# fulldrive2.net
KiCad netlist of a schematic drawn in EAGLE
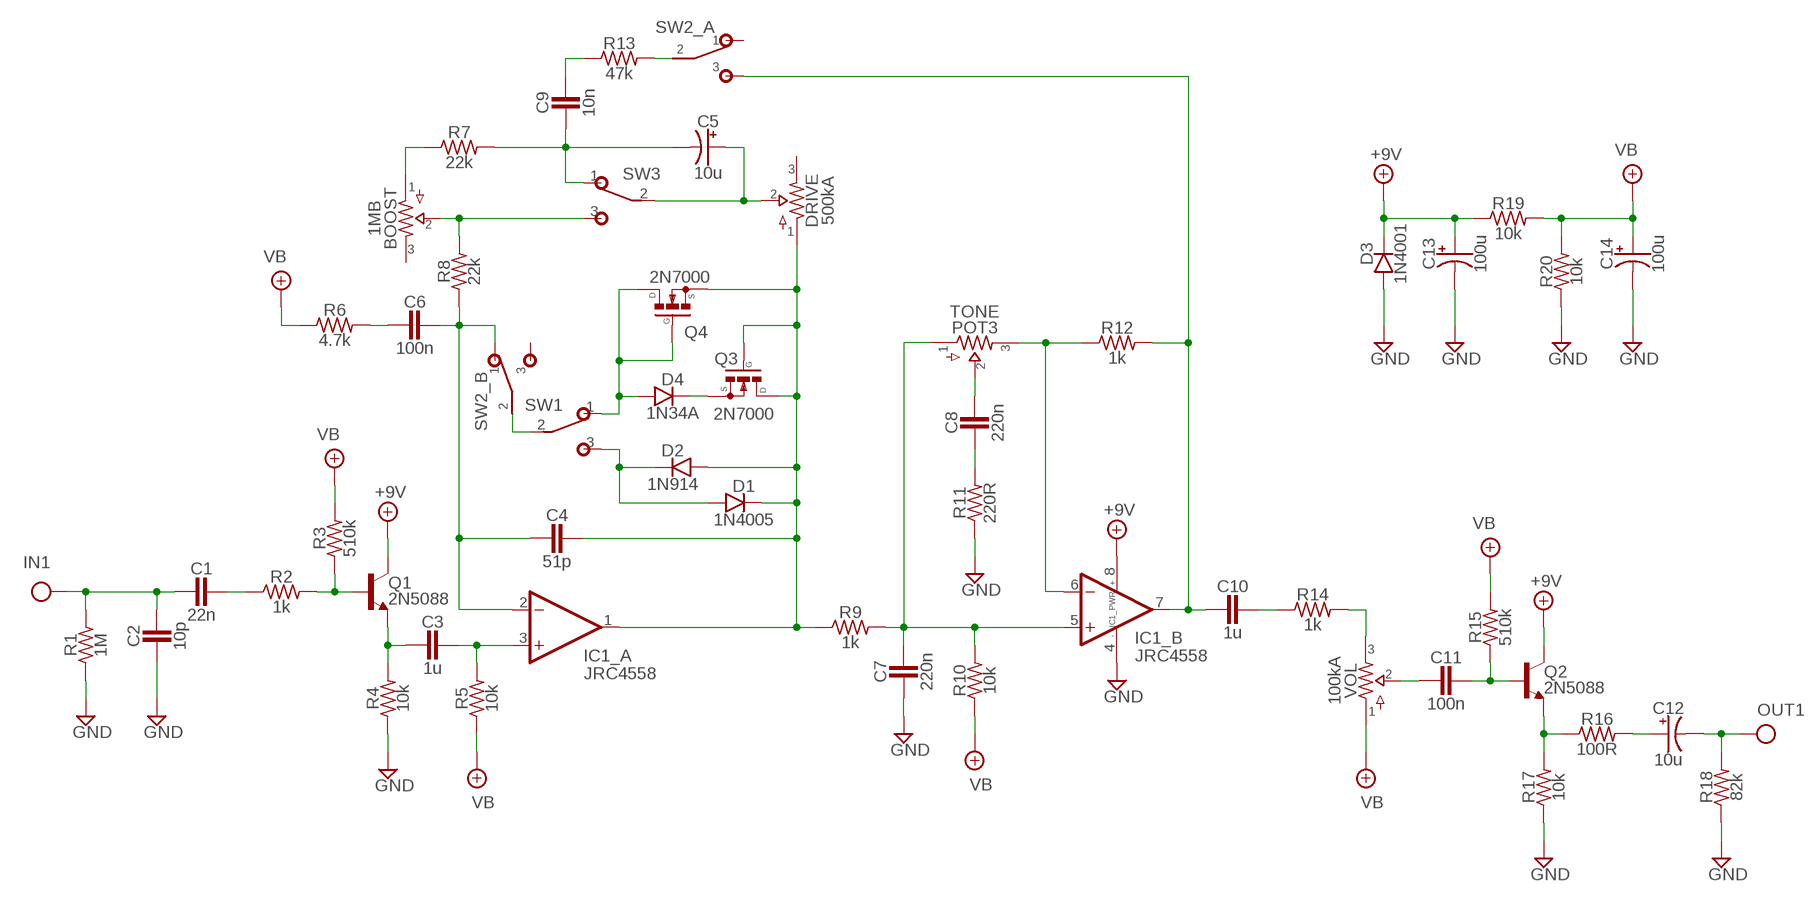
[diagram p0: schematic, sheet 1]

(export (version "E")
  (design (tool "Eeschema 10.0.6"))
  (components
    (comp (ref "BOOST")
      (value "1MB")
      (footprint "eagle-import:16MM")
      (libsource (lib "eagle-import") (part "POTS16MM"))
    )
    (comp (ref "C1")
      (value "22n")
      (footprint "eagle-import:BOX_SMALL")
      (libsource (lib "eagle-import") (part "CER/FILMBOX.1"))
    )
    (comp (ref "C2")
      (value "10p")
      (footprint "eagle-import:BOX_SMALL")
      (libsource (lib "eagle-import") (part "CER/FILMBOX.1"))
    )
    (comp (ref "C3")
      (value "1u")
      (footprint "eagle-import:BOX_SMALL")
      (libsource (lib "eagle-import") (part "CER/FILMBOX.1"))
    )
    (comp (ref "C4")
      (value "51p")
      (footprint "eagle-import:BOX_SMALL")
      (libsource (lib "eagle-import") (part "CER/FILMBOX.1"))
    )
    (comp (ref "C5")
      (value "10u")
      (footprint "eagle-import:050_020")
      (libsource (lib "eagle-import") (part "0500"))
    )
    (comp (ref "C6")
      (value "100n")
      (footprint "eagle-import:BOX_SMALL")
      (libsource (lib "eagle-import") (part "CER/FILMBOX.1"))
    )
    (comp (ref "C7")
      (value "220n")
      (footprint "eagle-import:BOX_SMALL")
      (libsource (lib "eagle-import") (part "CER/FILMBOX.1"))
    )
    (comp (ref "C8")
      (value "220n")
      (footprint "eagle-import:BOX_SMALL")
      (libsource (lib "eagle-import") (part "CER/FILMBOX.1"))
    )
    (comp (ref "C9")
      (value "10n")
      (footprint "eagle-import:BOX_SMALL")
      (libsource (lib "eagle-import") (part "CER/FILMBOX.1"))
    )
    (comp (ref "C10")
      (value "1u")
      (footprint "eagle-import:BOX_SMALL")
      (libsource (lib "eagle-import") (part "CER/FILMBOX.1"))
    )
    (comp (ref "C11")
      (value "100n")
      (footprint "eagle-import:BOX_SMALL")
      (libsource (lib "eagle-import") (part "CER/FILMBOX.1"))
    )
    (comp (ref "C12")
      (value "10u")
      (footprint "eagle-import:050_020")
      (libsource (lib "eagle-import") (part "0500"))
    )
    (comp (ref "C13")
      (value "100u")
      (footprint "eagle-import:050_020")
      (libsource (lib "eagle-import") (part "0500"))
    )
    (comp (ref "C14")
      (value "100u")
      (footprint "eagle-import:050_020")
      (libsource (lib "eagle-import") (part "0500"))
    )
    (comp (ref "D1")
      (value "1N4005")
      (footprint "eagle-import:DO35-2")
      (libsource (lib "eagle-import") (part "DO35.2"))
    )
    (comp (ref "D2")
      (value "1N914")
      (footprint "eagle-import:DO35-2")
      (libsource (lib "eagle-import") (part "DO35.2"))
    )
    (comp (ref "D3")
      (value "1N4001")
      (footprint "eagle-import:DO35-3")
      (libsource (lib "eagle-import") (part "DO35.3"))
    )
    (comp (ref "D4")
      (value "1N34A")
      (footprint "eagle-import:DO35-2")
      (libsource (lib "eagle-import") (part "DO35.2"))
    )
    (comp (ref "DRIVE")
      (value "500kA")
      (footprint "eagle-import:16MM")
      (libsource (lib "eagle-import") (part "POTS16MM"))
    )
    (comp (ref "IC1")
      (value "JRC4558")
      (footprint "eagle-import:DIL0")
      (libsource (lib "eagle-import") (part "DUALTH"))
    )
    (comp (ref "POT3")
      (value "TONE")
      (footprint "eagle-import:16MM")
      (libsource (lib "eagle-import") (part "POTS16MM"))
    )
    (comp (ref "Q1")
      (value "2N5088")
      (footprint "eagle-import:TO92-")
      (libsource (lib "eagle-import") (part "2N5088"))
    )
    (comp (ref "Q2")
      (value "2N5088")
      (footprint "eagle-import:TO92-")
      (libsource (lib "eagle-import") (part "2N5088"))
    )
    (comp (ref "Q3")
      (value "2N7000")
      (footprint "eagle-import:TO92-")
      (libsource (lib "eagle-import") (part "2N7000"))
    )
    (comp (ref "Q4")
      (value "2N7000")
      (footprint "eagle-import:TO92-")
      (libsource (lib "eagle-import") (part "2N7000"))
    )
    (comp (ref "R1")
      (value "1M")
      (footprint "eagle-import:R0207_3")
      (libsource (lib "eagle-import") (part "R_.3B"))
    )
    (comp (ref "R2")
      (value "1k")
      (footprint "eagle-import:R0207_3")
      (libsource (lib "eagle-import") (part "R_.3B"))
    )
    (comp (ref "R3")
      (value "510k")
      (footprint "eagle-import:R0207_3")
      (libsource (lib "eagle-import") (part "R_.3B"))
    )
    (comp (ref "R4")
      (value "10k")
      (footprint "eagle-import:R0207_3")
      (libsource (lib "eagle-import") (part "R_.3B"))
    )
    (comp (ref "R5")
      (value "10k")
      (footprint "eagle-import:R0207_3")
      (libsource (lib "eagle-import") (part "R_.3B"))
    )
    (comp (ref "R6")
      (value "4.7k")
      (footprint "eagle-import:R0207_3")
      (libsource (lib "eagle-import") (part "R_.3B"))
    )
    (comp (ref "R7")
      (value "22k")
      (footprint "eagle-import:R0207_3")
      (libsource (lib "eagle-import") (part "R_.3B"))
    )
    (comp (ref "R8")
      (value "22k")
      (footprint "eagle-import:R0207_3")
      (libsource (lib "eagle-import") (part "R_.3B"))
    )
    (comp (ref "R9")
      (value "1k")
      (footprint "eagle-import:R0207_3")
      (libsource (lib "eagle-import") (part "R_.3B"))
    )
    (comp (ref "R10")
      (value "10k")
      (footprint "eagle-import:R0207_3")
      (libsource (lib "eagle-import") (part "R_.3B"))
    )
    (comp (ref "R11")
      (value "220R")
      (footprint "eagle-import:R0207_3")
      (libsource (lib "eagle-import") (part "R_.3B"))
    )
    (comp (ref "R12")
      (value "1k")
      (footprint "eagle-import:R0207_3")
      (libsource (lib "eagle-import") (part "R_.3B"))
    )
    (comp (ref "R13")
      (value "47k")
      (footprint "eagle-import:R0207_3")
      (libsource (lib "eagle-import") (part "R_.3B"))
    )
    (comp (ref "R14")
      (value "1k")
      (footprint "eagle-import:R0207_3")
      (libsource (lib "eagle-import") (part "R_.3B"))
    )
    (comp (ref "R15")
      (value "510k")
      (footprint "eagle-import:R0207_3")
      (libsource (lib "eagle-import") (part "R_.3B"))
    )
    (comp (ref "R16")
      (value "100R")
      (footprint "eagle-import:R0207_3")
      (libsource (lib "eagle-import") (part "R_.3B"))
    )
    (comp (ref "R17")
      (value "10k")
      (footprint "eagle-import:R0207_3")
      (libsource (lib "eagle-import") (part "R_.3B"))
    )
    (comp (ref "R18")
      (value "82k")
      (footprint "eagle-import:R0207_3")
      (libsource (lib "eagle-import") (part "R_.3B"))
    )
    (comp (ref "R19")
      (value "10k")
      (footprint "eagle-import:R0207_3")
      (libsource (lib "eagle-import") (part "R_.3B"))
    )
    (comp (ref "R20")
      (value "10k")
      (footprint "eagle-import:R0207_3")
      (libsource (lib "eagle-import") (part "R_.3B"))
    )
    (comp (ref "SW1")
      (value "SPDT")
      (footprint "eagle-import:M9040P")
      (libsource (lib "eagle-import") (part "SPDT"))
    )
    (comp (ref "SW2")
      (value "DPDT")
      (footprint "eagle-import:DPDT")
      (libsource (lib "eagle-import") (part "DPDT"))
    )
    (comp (ref "SW3")
      (value "SPDT")
      (footprint "eagle-import:M9040P")
      (libsource (lib "eagle-import") (part "SPDT"))
    )
    (comp (ref "VOL")
      (value "100kA")
      (footprint "eagle-import:16MM")
      (libsource (lib "eagle-import") (part "POTS16MM"))
    )
  )
  (nets
    (net (code "1") (name "+9V") (class "Default")
      (node (ref "C13") (pin "+") (pinfunction "+_+") (pintype "passive"))
      (node (ref "D3") (pin "C") (pinfunction "C_C") (pintype "passive"))
      (node (ref "IC1") (pin "8") (pinfunction "V+_8") (pintype "power_in"))
      (node (ref "Q1") (pin "1") (pinfunction "C_1") (pintype "passive"))
      (node (ref "Q2") (pin "1") (pinfunction "C_1") (pintype "passive"))
      (node (ref "R19") (pin "1") (pinfunction "1_1") (pintype "passive"))
    )
    (net (code "2") (name "GND") (class "Default")
      (node (ref "C13") (pin "-") (pinfunction "-_-") (pintype "passive"))
      (node (ref "C14") (pin "-") (pinfunction "-_-") (pintype "passive"))
      (node (ref "C2") (pin "2") (pinfunction "2_2") (pintype "passive"))
      (node (ref "C7") (pin "2") (pinfunction "2_2") (pintype "passive"))
      (node (ref "D3") (pin "A") (pinfunction "A_A") (pintype "passive"))
      (node (ref "IC1") (pin "4") (pinfunction "V-_4") (pintype "power_in"))
      (node (ref "R1") (pin "1") (pinfunction "1_1") (pintype "passive"))
      (node (ref "R11") (pin "1") (pinfunction "1_1") (pintype "passive"))
      (node (ref "R17") (pin "1") (pinfunction "1_1") (pintype "passive"))
      (node (ref "R18") (pin "1") (pinfunction "1_1") (pintype "passive"))
      (node (ref "R20") (pin "1") (pinfunction "1_1") (pintype "passive"))
      (node (ref "R4") (pin "1") (pinfunction "1_1") (pintype "passive"))
    )
    (net (code "3") (name "IN") (class "Default")
      (node (ref "C1") (pin "2") (pinfunction "2_2") (pintype "passive"))
      (node (ref "C2") (pin "1") (pinfunction "1_1") (pintype "passive"))
      (node (ref "R1") (pin "2") (pinfunction "2_2") (pintype "passive"))
    )
    (net (code "4") (name "Net-(BOOST-Pad1)") (class "Default")
      (node (ref "BOOST") (pin "1") (pinfunction "1_1") (pintype "passive"))
      (node (ref "R7") (pin "1") (pinfunction "1_1") (pintype "passive"))
    )
    (net (code "5") (name "Net-(C1-Pad1)") (class "Default")
      (node (ref "C1") (pin "1") (pinfunction "1_1") (pintype "passive"))
      (node (ref "R2") (pin "1") (pinfunction "1_1") (pintype "passive"))
    )
    (net (code "6") (name "Net-(C6-Pad2)") (class "Default")
      (node (ref "C6") (pin "2") (pinfunction "2_2") (pintype "passive"))
      (node (ref "R6") (pin "2") (pinfunction "2_2") (pintype "passive"))
    )
    (net (code "7") (name "Net-(C8-Pad1)") (class "Default")
      (node (ref "C8") (pin "1") (pinfunction "1_1") (pintype "passive"))
      (node (ref "POT3") (pin "2") (pinfunction "2_2") (pintype "passive"))
    )
    (net (code "8") (name "Net-(C8-Pad2)") (class "Default")
      (node (ref "C8") (pin "2") (pinfunction "2_2") (pintype "passive"))
      (node (ref "R11") (pin "2") (pinfunction "2_2") (pintype "passive"))
    )
    (net (code "9") (name "Net-(C9-Pad1)") (class "Default")
      (node (ref "C9") (pin "1") (pinfunction "1_1") (pintype "passive"))
      (node (ref "R13") (pin "1") (pinfunction "1_1") (pintype "passive"))
    )
    (net (code "10") (name "Net-(C10-Pad1)") (class "Default")
      (node (ref "C10") (pin "1") (pinfunction "1_1") (pintype "passive"))
      (node (ref "R14") (pin "1") (pinfunction "1_1") (pintype "passive"))
    )
    (net (code "11") (name "Net-(C11-Pad2)") (class "Default")
      (node (ref "C11") (pin "2") (pinfunction "2_2") (pintype "passive"))
      (node (ref "VOL") (pin "2") (pinfunction "2_2") (pintype "passive"))
    )
    (net (code "12") (name "Net-(C12-Pad+)") (class "Default")
      (node (ref "C12") (pin "+") (pinfunction "+_+") (pintype "passive"))
      (node (ref "R16") (pin "2") (pinfunction "2_2") (pintype "passive"))
    )
    (net (code "13") (name "Net-(IC1A-+IN)") (class "Default")
      (node (ref "C3") (pin "1") (pinfunction "1_1") (pintype "passive"))
      (node (ref "IC1") (pin "3") (pinfunction "+IN_3") (pintype "input"))
      (node (ref "R5") (pin "2") (pinfunction "2_2") (pintype "passive"))
    )
    (net (code "14") (name "Net-(IC1A--IN)") (class "Default")
      (node (ref "C4") (pin "2") (pinfunction "2_2") (pintype "passive"))
      (node (ref "C6") (pin "1") (pinfunction "1_1") (pintype "passive"))
      (node (ref "IC1") (pin "2") (pinfunction "-IN_2") (pintype "input"))
      (node (ref "R8") (pin "1") (pinfunction "1_1") (pintype "passive"))
      (node (ref "SW2") (pin "B1") (pinfunction "1_B1") (pintype "passive"))
    )
    (net (code "15") (name "Net-(IC1A-OUT)") (class "Default")
      (node (ref "C4") (pin "1") (pinfunction "1_1") (pintype "passive"))
      (node (ref "D1") (pin "C") (pinfunction "C_C") (pintype "passive"))
      (node (ref "D2") (pin "A") (pinfunction "A_A") (pintype "passive"))
      (node (ref "DRIVE") (pin "1") (pinfunction "1_1") (pintype "passive"))
      (node (ref "IC1") (pin "1") (pinfunction "OUT_1") (pintype "output"))
      (node (ref "Q3") (pin "1") (pinfunction "D_1") (pintype "passive"))
      (node (ref "Q3") (pin "2") (pinfunction "G_2") (pintype "passive"))
      (node (ref "Q4") (pin "3") (pinfunction "S_3") (pintype "passive"))
      (node (ref "R9") (pin "1") (pinfunction "1_1") (pintype "passive"))
    )
    (net (code "16") (name "Net-(IC1B-+IN)") (class "Default")
      (node (ref "C7") (pin "1") (pinfunction "1_1") (pintype "passive"))
      (node (ref "IC1") (pin "5") (pinfunction "+IN_5") (pintype "input"))
      (node (ref "POT3") (pin "1") (pinfunction "1_1") (pintype "passive"))
      (node (ref "R10") (pin "2") (pinfunction "2_2") (pintype "passive"))
      (node (ref "R9") (pin "2") (pinfunction "2_2") (pintype "passive"))
    )
    (net (code "17") (name "Net-(IC1B--IN)") (class "Default")
      (node (ref "IC1") (pin "6") (pinfunction "-IN_6") (pintype "input"))
      (node (ref "POT3") (pin "3") (pinfunction "3_3") (pintype "passive"))
      (node (ref "R12") (pin "1") (pinfunction "1_1") (pintype "passive"))
    )
    (net (code "18") (name "Net-(IC1B-OUT)") (class "Default")
      (node (ref "C10") (pin "2") (pinfunction "2_2") (pintype "passive"))
      (node (ref "IC1") (pin "7") (pinfunction "OUT_7") (pintype "output"))
      (node (ref "R12") (pin "2") (pinfunction "2_2") (pintype "passive"))
      (node (ref "SW2") (pin "A3") (pinfunction "3_A3") (pintype "passive"))
    )
    (net (code "19") (name "Net-(Q1-B)") (class "Default")
      (node (ref "Q1") (pin "2") (pinfunction "B_2") (pintype "passive"))
      (node (ref "R2") (pin "2") (pinfunction "2_2") (pintype "passive"))
      (node (ref "R3") (pin "1") (pinfunction "1_1") (pintype "passive"))
    )
    (net (code "20") (name "Net-(Q1-E)") (class "Default")
      (node (ref "C3") (pin "2") (pinfunction "2_2") (pintype "passive"))
      (node (ref "Q1") (pin "3") (pinfunction "E_3") (pintype "passive"))
      (node (ref "R4") (pin "2") (pinfunction "2_2") (pintype "passive"))
    )
    (net (code "21") (name "Net-(Q2-B)") (class "Default")
      (node (ref "C11") (pin "1") (pinfunction "1_1") (pintype "passive"))
      (node (ref "Q2") (pin "2") (pinfunction "B_2") (pintype "passive"))
      (node (ref "R15") (pin "1") (pinfunction "1_1") (pintype "passive"))
    )
    (net (code "22") (name "Net-(Q2-E)") (class "Default")
      (node (ref "Q2") (pin "3") (pinfunction "E_3") (pintype "passive"))
      (node (ref "R16") (pin "1") (pinfunction "1_1") (pintype "passive"))
      (node (ref "R17") (pin "2") (pinfunction "2_2") (pintype "passive"))
    )
    (net (code "23") (name "Net-(Q3-S)") (class "Default")
      (node (ref "D4") (pin "C") (pinfunction "C_C") (pintype "passive"))
      (node (ref "Q3") (pin "3") (pinfunction "S_3") (pintype "passive"))
    )
    (net (code "24") (name "Net-(Q4-D)") (class "Default")
      (node (ref "D4") (pin "A") (pinfunction "A_A") (pintype "passive"))
      (node (ref "Q4") (pin "1") (pinfunction "D_1") (pintype "passive"))
      (node (ref "Q4") (pin "2") (pinfunction "G_2") (pintype "passive"))
      (node (ref "SW1") (pin "1") (pinfunction "O_1") (pintype "passive"))
    )
    (net (code "25") (name "Net-(R14-Pad2)") (class "Default")
      (node (ref "R14") (pin "2") (pinfunction "2_2") (pintype "passive"))
      (node (ref "VOL") (pin "3") (pinfunction "3_3") (pintype "passive"))
    )
    (net (code "26") (name "Net-(SW1-P)") (class "Default")
      (node (ref "SW1") (pin "2") (pinfunction "P_2") (pintype "passive"))
      (node (ref "SW2") (pin "B2") (pinfunction "2_B2") (pintype "passive"))
    )
    (net (code "27") (name "Net-(SW1-S)") (class "Default")
      (node (ref "D1") (pin "A") (pinfunction "A_A") (pintype "passive"))
      (node (ref "D2") (pin "C") (pinfunction "C_C") (pintype "passive"))
      (node (ref "SW1") (pin "3") (pinfunction "S_3") (pintype "passive"))
    )
    (net (code "28") (name "Net-(SW2A-2)") (class "Default")
      (node (ref "R13") (pin "2") (pinfunction "2_2") (pintype "passive"))
      (node (ref "SW2") (pin "A2") (pinfunction "2_A2") (pintype "passive"))
    )
    (net (code "29") (name "Net-(SW3-O)") (class "Default")
      (node (ref "C5") (pin "-") (pinfunction "-_-") (pintype "passive"))
      (node (ref "C9") (pin "2") (pinfunction "2_2") (pintype "passive"))
      (node (ref "R7") (pin "2") (pinfunction "2_2") (pintype "passive"))
      (node (ref "SW3") (pin "1") (pinfunction "O_1") (pintype "passive"))
    )
    (net (code "30") (name "Net-(SW3-P)") (class "Default")
      (node (ref "C5") (pin "+") (pinfunction "+_+") (pintype "passive"))
      (node (ref "DRIVE") (pin "2") (pinfunction "2_2") (pintype "passive"))
      (node (ref "SW3") (pin "2") (pinfunction "P_2") (pintype "passive"))
    )
    (net (code "31") (name "Net-(SW3-S)") (class "Default")
      (node (ref "BOOST") (pin "2") (pinfunction "2_2") (pintype "passive"))
      (node (ref "R8") (pin "2") (pinfunction "2_2") (pintype "passive"))
      (node (ref "SW3") (pin "3") (pinfunction "S_3") (pintype "passive"))
    )
    (net (code "32") (name "OUT") (class "Default")
      (node (ref "C12") (pin "-") (pinfunction "-_-") (pintype "passive"))
      (node (ref "R18") (pin "2") (pinfunction "2_2") (pintype "passive"))
    )
    (net (code "33") (name "VB") (class "Default")
      (node (ref "C14") (pin "+") (pinfunction "+_+") (pintype "passive"))
      (node (ref "R10") (pin "1") (pinfunction "1_1") (pintype "passive"))
      (node (ref "R15") (pin "2") (pinfunction "2_2") (pintype "passive"))
      (node (ref "R19") (pin "2") (pinfunction "2_2") (pintype "passive"))
      (node (ref "R20") (pin "2") (pinfunction "2_2") (pintype "passive"))
      (node (ref "R3") (pin "2") (pinfunction "2_2") (pintype "passive"))
      (node (ref "R5") (pin "1") (pinfunction "1_1") (pintype "passive"))
      (node (ref "R6") (pin "1") (pinfunction "1_1") (pintype "passive"))
      (node (ref "VOL") (pin "1") (pinfunction "1_1") (pintype "passive"))
    )
    (net (code "34") (name "unconnected-(BOOST-Pad3)") (class "Default")
      (node (ref "BOOST") (pin "3") (pinfunction "3_3") (pintype "passive"))
    )
    (net (code "35") (name "unconnected-(DRIVE-Pad3)") (class "Default")
      (node (ref "DRIVE") (pin "3") (pinfunction "3_3") (pintype "passive"))
    )
    (net (code "36") (name "unconnected-(SW2A-1-PadA1)") (class "Default")
      (node (ref "SW2") (pin "A1") (pinfunction "1_A1") (pintype "passive"))
    )
    (net (code "37") (name "unconnected-(SW2B-3-PadB3)") (class "Default")
      (node (ref "SW2") (pin "B3") (pinfunction "3_B3") (pintype "passive"))
    )
  )
)
